# 01_LSH-100.net
KiCad netlist of a schematic drawn in Altium Designer
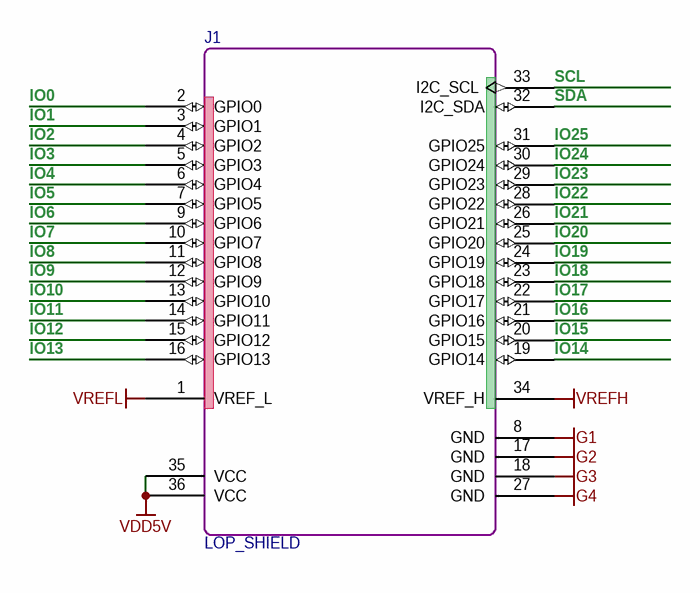
[diagram p0: 01_LSH-100.SchDoc]

(export (version "E")
  (design (tool "Eeschema 10.0.6"))
  (components
    (comp (ref "J1")
      (value "LOP_SHIELD")
      (footprint "LOP_SHIELD_MOD")
      (description "Lophilo Shield Module Slot")
      (fields (field (name "PUBLISHER") "Cowin") (field (name "DESIGNER") "shyul"))
      (libsource (lib "PCB_LSH-100") (part "LOP_SHIELD_MOD"))
    )
  )
  (nets
    (net (code "1") (name "/IO0") (class "Default")
      (node (ref "J1") (pin "2") (pinfunction "GPIO0_2") (pintype "bidirectional"))
    )
    (net (code "2") (name "/IO1") (class "Default")
      (node (ref "J1") (pin "3") (pinfunction "GPIO1_3") (pintype "bidirectional"))
    )
    (net (code "3") (name "/IO2") (class "Default")
      (node (ref "J1") (pin "4") (pinfunction "GPIO2_4") (pintype "bidirectional"))
    )
    (net (code "4") (name "/IO3") (class "Default")
      (node (ref "J1") (pin "5") (pinfunction "GPIO3_5") (pintype "bidirectional"))
    )
    (net (code "5") (name "/IO4") (class "Default")
      (node (ref "J1") (pin "6") (pinfunction "GPIO4_6") (pintype "bidirectional"))
    )
    (net (code "6") (name "/IO5") (class "Default")
      (node (ref "J1") (pin "7") (pinfunction "GPIO5_7") (pintype "bidirectional"))
    )
    (net (code "7") (name "/IO6") (class "Default")
      (node (ref "J1") (pin "9") (pinfunction "GPIO6_9") (pintype "bidirectional"))
    )
    (net (code "8") (name "/IO7") (class "Default")
      (node (ref "J1") (pin "10") (pinfunction "GPIO7_10") (pintype "bidirectional"))
    )
    (net (code "9") (name "/IO8") (class "Default")
      (node (ref "J1") (pin "11") (pinfunction "GPIO8_11") (pintype "bidirectional"))
    )
    (net (code "10") (name "/IO9") (class "Default")
      (node (ref "J1") (pin "12") (pinfunction "GPIO9_12") (pintype "bidirectional"))
    )
    (net (code "11") (name "/IO10") (class "Default")
      (node (ref "J1") (pin "13") (pinfunction "GPIO10_13") (pintype "bidirectional"))
    )
    (net (code "12") (name "/IO11") (class "Default")
      (node (ref "J1") (pin "14") (pinfunction "GPIO11_14") (pintype "bidirectional"))
    )
    (net (code "13") (name "/IO12") (class "Default")
      (node (ref "J1") (pin "15") (pinfunction "GPIO12_15") (pintype "bidirectional"))
    )
    (net (code "14") (name "/IO13") (class "Default")
      (node (ref "J1") (pin "16") (pinfunction "GPIO13_16") (pintype "bidirectional"))
    )
    (net (code "15") (name "/IO14") (class "Default")
      (node (ref "J1") (pin "19") (pinfunction "GPIO14_19") (pintype "bidirectional"))
    )
    (net (code "16") (name "/IO15") (class "Default")
      (node (ref "J1") (pin "20") (pinfunction "GPIO15_20") (pintype "bidirectional"))
    )
    (net (code "17") (name "/IO16") (class "Default")
      (node (ref "J1") (pin "21") (pinfunction "GPIO16_21") (pintype "bidirectional"))
    )
    (net (code "18") (name "/IO17") (class "Default")
      (node (ref "J1") (pin "22") (pinfunction "GPIO17_22") (pintype "bidirectional"))
    )
    (net (code "19") (name "/IO18") (class "Default")
      (node (ref "J1") (pin "23") (pinfunction "GPIO18_23") (pintype "bidirectional"))
    )
    (net (code "20") (name "/IO19") (class "Default")
      (node (ref "J1") (pin "24") (pinfunction "GPIO19_24") (pintype "bidirectional"))
    )
    (net (code "21") (name "/IO20") (class "Default")
      (node (ref "J1") (pin "25") (pinfunction "GPIO20_25") (pintype "bidirectional"))
    )
    (net (code "22") (name "/IO21") (class "Default")
      (node (ref "J1") (pin "26") (pinfunction "GPIO21_26") (pintype "bidirectional"))
    )
    (net (code "23") (name "/IO22") (class "Default")
      (node (ref "J1") (pin "28") (pinfunction "GPIO22_28") (pintype "bidirectional"))
    )
    (net (code "24") (name "/IO23") (class "Default")
      (node (ref "J1") (pin "29") (pinfunction "GPIO23_29") (pintype "bidirectional"))
    )
    (net (code "25") (name "/IO24") (class "Default")
      (node (ref "J1") (pin "30") (pinfunction "GPIO24_30") (pintype "bidirectional"))
    )
    (net (code "26") (name "/IO25") (class "Default")
      (node (ref "J1") (pin "31") (pinfunction "GPIO25_31") (pintype "bidirectional"))
    )
    (net (code "27") (name "/SCL") (class "Default")
      (node (ref "J1") (pin "33") (pinfunction "I2C_SCL_33") (pintype "output"))
    )
    (net (code "28") (name "/SDA") (class "Default")
      (node (ref "J1") (pin "32") (pinfunction "I2C_SDA_32") (pintype "bidirectional"))
    )
    (net (code "29") (name "G1") (class "Default")
      (node (ref "J1") (pin "8") (pinfunction "GND_8") (pintype "passive"))
    )
    (net (code "30") (name "G2") (class "Default")
      (node (ref "J1") (pin "17") (pinfunction "GND_17") (pintype "passive"))
    )
    (net (code "31") (name "G3") (class "Default")
      (node (ref "J1") (pin "18") (pinfunction "GND_18") (pintype "passive"))
    )
    (net (code "32") (name "G4") (class "Default")
      (node (ref "J1") (pin "27") (pinfunction "GND_27") (pintype "passive"))
    )
    (net (code "33") (name "VDD5V") (class "Default")
      (node (ref "J1") (pin "35") (pinfunction "VCC_35") (pintype "power_in"))
      (node (ref "J1") (pin "36") (pinfunction "VCC_36") (pintype "power_in"))
    )
    (net (code "34") (name "VREFH") (class "Default")
      (node (ref "J1") (pin "34") (pinfunction "VREF_H_34") (pintype "passive"))
    )
    (net (code "35") (name "VREFL") (class "Default")
      (node (ref "J1") (pin "1") (pinfunction "VREF_L_1") (pintype "passive"))
    )
  )
)
